# Spring12_6_Node.net
KiCad netlist of a schematic drawn in EAGLE
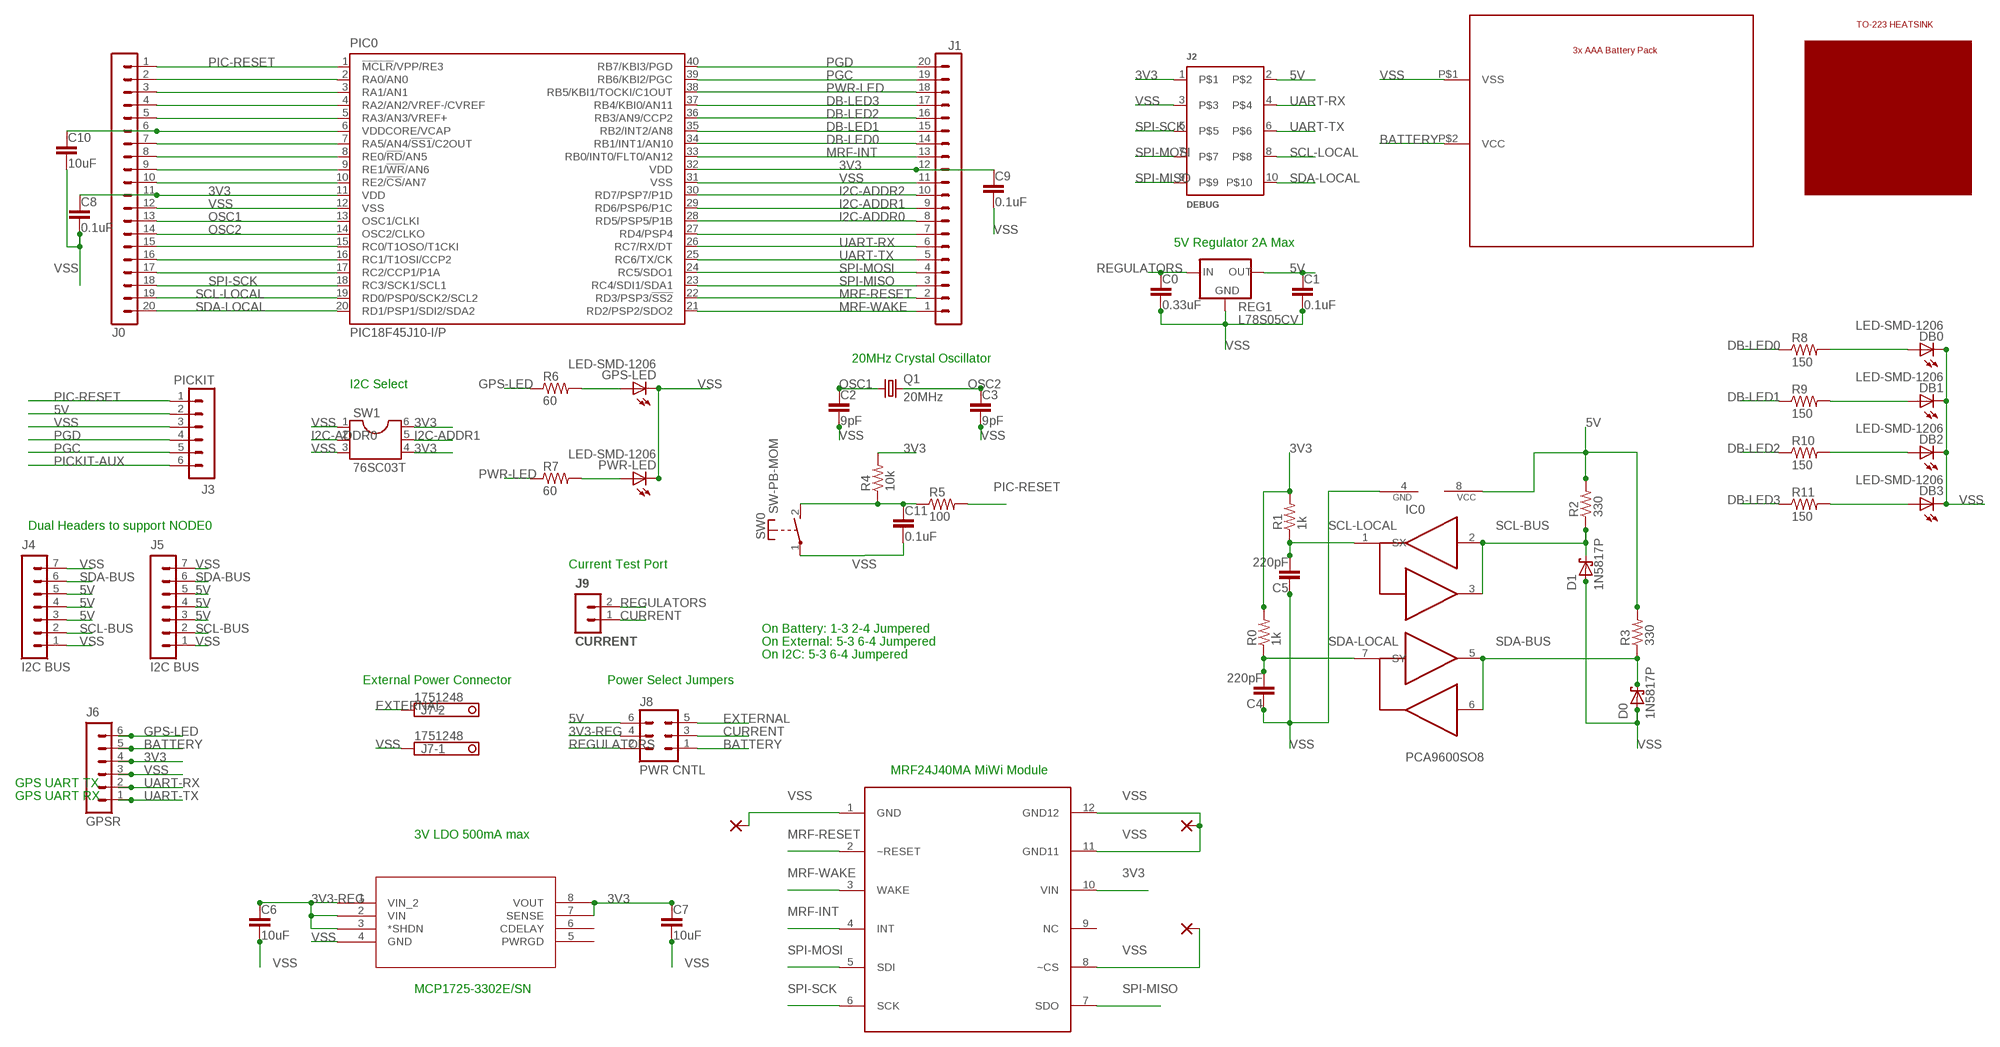
[diagram p0: schematic, sheet 1]

(export (version "E")
  (design (tool "Eeschema 10.0.6"))
  (components
    (comp (ref "BATT0")
      (value "2479-BATTERY")
      (footprint "eagle-import:2479-BATTERY")
      (libsource (lib "eagle-import") (part "2479-BATTERY"))
    )
    (comp (ref "C0")
      (value "0.33uF")
      (footprint "eagle-import:C2.5-5")
      (libsource (lib "eagle-import") (part "C2.5-5"))
    )
    (comp (ref "C1")
      (value "0.1uF")
      (footprint "eagle-import:C2.5-5")
      (libsource (lib "eagle-import") (part "C2.5-5"))
    )
    (comp (ref "C2")
      (value "9pF")
      (footprint "eagle-import:C2.5-5")
      (libsource (lib "eagle-import") (part "C2.5-5"))
    )
    (comp (ref "C3")
      (value "9pF")
      (footprint "eagle-import:C2.5-5")
      (libsource (lib "eagle-import") (part "C2.5-5"))
    )
    (comp (ref "C4")
      (value "220pF")
      (footprint "eagle-import:C2.5-5")
      (libsource (lib "eagle-import") (part "C2.5-5"))
    )
    (comp (ref "C5")
      (value "220pF")
      (footprint "eagle-import:C2.5-5")
      (libsource (lib "eagle-import") (part "C2.5-5"))
    )
    (comp (ref "C6")
      (value "10uF")
      (footprint "eagle-import:C2.5-5")
      (libsource (lib "eagle-import") (part "C2.5-5"))
    )
    (comp (ref "C7")
      (value "10uF")
      (footprint "eagle-import:C2.5-5")
      (libsource (lib "eagle-import") (part "C2.5-5"))
    )
    (comp (ref "C8")
      (value "0.1uF")
      (footprint "eagle-import:C2.5-5")
      (libsource (lib "eagle-import") (part "C2.5-5"))
    )
    (comp (ref "C9")
      (value "0.1uF")
      (footprint "eagle-import:C2.5-5")
      (libsource (lib "eagle-import") (part "C2.5-5"))
    )
    (comp (ref "C10")
      (value "10uF")
      (footprint "eagle-import:C2.5-5")
      (libsource (lib "eagle-import") (part "C2.5-5"))
    )
    (comp (ref "C11")
      (value "0.1uF")
      (footprint "eagle-import:C2.5-5")
      (libsource (lib "eagle-import") (part "C2.5-5"))
    )
    (comp (ref "D0")
      (value "1N5817P")
      (footprint "eagle-import:1N5817")
      (libsource (lib "eagle-import") (part "1N5817P"))
    )
    (comp (ref "D1")
      (value "1N5817P")
      (footprint "eagle-import:1N5817")
      (libsource (lib "eagle-import") (part "1N5817P"))
    )
    (comp (ref "DB0")
      (value "LED-SMD-1206")
      (footprint "eagle-import:LED1206")
      (libsource (lib "eagle-import") (part "LED-SMD-1206"))
    )
    (comp (ref "DB1")
      (value "LED-SMD-1206")
      (footprint "eagle-import:LED1206")
      (libsource (lib "eagle-import") (part "LED-SMD-1206"))
    )
    (comp (ref "DB2")
      (value "LED-SMD-1206")
      (footprint "eagle-import:LED1206")
      (libsource (lib "eagle-import") (part "LED-SMD-1206"))
    )
    (comp (ref "DB3")
      (value "LED-SMD-1206")
      (footprint "eagle-import:LED1206")
      (libsource (lib "eagle-import") (part "LED-SMD-1206"))
    )
    (comp (ref "GPS-LED")
      (value "LED-SMD-1206")
      (footprint "eagle-import:LED1206")
      (libsource (lib "eagle-import") (part "LED-SMD-1206"))
    )
    (comp (ref "IC0")
      (value "PCA9600SO8")
      (footprint "eagle-import:SO08")
      (libsource (lib "eagle-import") (part "PCA9600SO8"))
    )
    (comp (ref "J0")
      (value "MA20-1")
      (footprint "eagle-import:MA20-1")
      (fields (field (name "OC_FARNELL") "unknown") (field (name "OC_NEWARK") "unknown"))
      (libsource (lib "eagle-import") (part "MA20-1"))
    )
    (comp (ref "J1")
      (value "MA20-1")
      (footprint "eagle-import:MA20-1")
      (fields (field (name "OC_FARNELL") "unknown") (field (name "OC_NEWARK") "unknown"))
      (libsource (lib "eagle-import") (part "MA20-1"))
    )
    (comp (ref "J2")
      (value "DEBUG")
      (footprint "eagle-import:2510-6002")
      (libsource (lib "eagle-import") (part "2510-6002"))
    )
    (comp (ref "J3")
      (value "PICKIT")
      (footprint "eagle-import:MA06-1")
      (libsource (lib "eagle-import") (part "MA06-1"))
    )
    (comp (ref "J4")
      (value "I2C BUS")
      (footprint "eagle-import:MA07-1")
      (libsource (lib "eagle-import") (part "MA07-1"))
    )
    (comp (ref "J5")
      (value "I2C BUS")
      (footprint "eagle-import:MA07-1")
      (libsource (lib "eagle-import") (part "MA07-1"))
    )
    (comp (ref "J6")
      (value "GPSR")
      (footprint "eagle-import:MA06-1")
      (libsource (lib "eagle-import") (part "MA06-1"))
    )
    (comp (ref "J7")
      (value "1751248")
      (footprint "eagle-import:1751248")
      (libsource (lib "eagle-import") (part "1751248"))
    )
    (comp (ref "J8")
      (value "PWR CNTL")
      (footprint "eagle-import:MA03-2")
      (libsource (lib "eagle-import") (part "MA03-2"))
    )
    (comp (ref "J9")
      (value "CURRENT")
      (footprint "eagle-import:MA02-1")
      (libsource (lib "eagle-import") (part "MA02-1"))
    )
    (comp (ref "PIC0")
      (value "PIC18F45J10-I/P")
      (footprint "eagle-import:DIL40")
      (libsource (lib "eagle-import") (part "PIC18F45J10-I/P"))
    )
    (comp (ref "PWR-LED")
      (value "LED-SMD-1206")
      (footprint "eagle-import:LED1206")
      (libsource (lib "eagle-import") (part "LED-SMD-1206"))
    )
    (comp (ref "Q1")
      (value "20MHz")
      (footprint "eagle-import:HC49U-V")
      (libsource (lib "eagle-import") (part "CRYSTALHC49U-V"))
    )
    (comp (ref "R0")
      (value "1k")
      (footprint "eagle-import:R-1_4W")
      (libsource (lib "eagle-import") (part "R-1/4W"))
    )
    (comp (ref "R1")
      (value "1k")
      (footprint "eagle-import:R-1_4W")
      (libsource (lib "eagle-import") (part "R-1/4W"))
    )
    (comp (ref "R2")
      (value "330")
      (footprint "eagle-import:R-1_4W")
      (libsource (lib "eagle-import") (part "R-1/4W"))
    )
    (comp (ref "R3")
      (value "330")
      (footprint "eagle-import:R-1_4W")
      (libsource (lib "eagle-import") (part "R-1/4W"))
    )
    (comp (ref "R4")
      (value "10k")
      (footprint "eagle-import:R1206")
      (libsource (lib "eagle-import") (part "R1206"))
    )
    (comp (ref "R5")
      (value "100")
      (footprint "eagle-import:R1206")
      (libsource (lib "eagle-import") (part "R1206"))
    )
    (comp (ref "R6")
      (value "60")
      (footprint "eagle-import:R1206")
      (libsource (lib "eagle-import") (part "R1206"))
    )
    (comp (ref "R7")
      (value "60")
      (footprint "eagle-import:R1206")
      (libsource (lib "eagle-import") (part "R1206"))
    )
    (comp (ref "R8")
      (value "150")
      (footprint "eagle-import:R1206")
      (libsource (lib "eagle-import") (part "R1206"))
    )
    (comp (ref "R9")
      (value "150")
      (footprint "eagle-import:R1206")
      (libsource (lib "eagle-import") (part "R1206"))
    )
    (comp (ref "R10")
      (value "150")
      (footprint "eagle-import:R1206")
      (libsource (lib "eagle-import") (part "R1206"))
    )
    (comp (ref "R11")
      (value "150")
      (footprint "eagle-import:R1206")
      (libsource (lib "eagle-import") (part "R1206"))
    )
    (comp (ref "REG0")
      (value "MCP1725-XXXXX/SN")
      (footprint "eagle-import:SOIC8-N_MC")
      (libsource (lib "eagle-import") (part "MCP1725-XXXXX/SN"))
    )
    (comp (ref "REG1")
      (value "L78S05CV")
      (footprint "eagle-import:78XXL")
      (libsource (lib "eagle-import") (part "78XXL"))
    )
    (comp (ref "RF0")
      (value "MRF24J40MA")
      (footprint "eagle-import:PCB12")
      (libsource (lib "eagle-import") (part "MRF24J40MA"))
    )
    (comp (ref "SW0")
      (value "SW-PB-MOM")
      (footprint "eagle-import:SW-MOM-PB")
      (libsource (lib "eagle-import") (part "SW-PB-MOM"))
    )
    (comp (ref "SW1")
      (value "76SC03T")
      (footprint "eagle-import:DIL06")
      (libsource (lib "eagle-import") (part "DIL6"))
    )
    (comp (ref "U$18")
      (value "VIA")
      (footprint "eagle-import:VIA")
      (libsource (lib "eagle-import") (part "VIA"))
    )
    (comp (ref "U$19")
      (value "VIA")
      (footprint "eagle-import:VIA")
      (libsource (lib "eagle-import") (part "VIA"))
    )
    (comp (ref "U$20")
      (value "VIA")
      (footprint "eagle-import:VIA")
      (libsource (lib "eagle-import") (part "VIA"))
    )
    (comp (ref "U$28")
      (value "7-361-BA")
      (footprint "eagle-import:7-361-BA")
      (libsource (lib "eagle-import") (part "7-361-BA"))
    )
  )
  (nets
    (net (code "1") (name "/3V3") (class "Default")
      (node (ref "C7") (pin "1") (pinfunction "1_1") (pintype "passive"))
      (node (ref "C8") (pin "1") (pinfunction "1_1") (pintype "passive"))
      (node (ref "C9") (pin "1") (pinfunction "1_1") (pintype "passive"))
      (node (ref "J0") (pin "11") (pinfunction "11_11") (pintype "passive"))
      (node (ref "J1") (pin "12") (pinfunction "12_12") (pintype "passive"))
      (node (ref "J2") (pin "1") (pinfunction "P$1_1") (pintype "passive"))
      (node (ref "J6") (pin "4") (pinfunction "4_4") (pintype "passive"))
      (node (ref "PIC0") (pin "11") (pinfunction "VDD_11") (pintype "power_in"))
      (node (ref "PIC0") (pin "32") (pinfunction "VDD_32") (pintype "power_in"))
      (node (ref "R0") (pin "2") (pinfunction "2_2") (pintype "passive"))
      (node (ref "R1") (pin "2") (pinfunction "2_2") (pintype "passive"))
      (node (ref "R4") (pin "2") (pinfunction "2_2") (pintype "passive"))
      (node (ref "REG0") (pin "7") (pinfunction "SENSE_7") (pintype "passive"))
      (node (ref "REG0") (pin "8") (pinfunction "VOUT_8") (pintype "passive"))
      (node (ref "RF0") (pin "10") (pinfunction "VIN_10") (pintype "bidirectional"))
      (node (ref "SW1") (pin "4") (pinfunction "4_4") (pintype "passive"))
      (node (ref "SW1") (pin "6") (pinfunction "6_6") (pintype "passive"))
    )
    (net (code "2") (name "/3V3-REG") (class "Default")
      (node (ref "C6") (pin "1") (pinfunction "1_1") (pintype "passive"))
      (node (ref "J8") (pin "4") (pinfunction "4_4") (pintype "passive"))
      (node (ref "REG0") (pin "1") (pinfunction "VIN_2_1") (pintype "passive"))
      (node (ref "REG0") (pin "2") (pinfunction "VIN_2") (pintype "passive"))
      (node (ref "REG0") (pin "3") (pinfunction "*SHDN_3") (pintype "passive"))
    )
    (net (code "3") (name "/5V") (class "Default")
      (node (ref "C1") (pin "1") (pinfunction "1_1") (pintype "passive"))
      (node (ref "IC0") (pin "8") (pinfunction "VCC_8") (pintype "power_in"))
      (node (ref "J2") (pin "2") (pinfunction "P$2_2") (pintype "passive"))
      (node (ref "J3") (pin "2") (pinfunction "2_2") (pintype "passive"))
      (node (ref "J4") (pin "3") (pinfunction "3_3") (pintype "passive"))
      (node (ref "J4") (pin "4") (pinfunction "4_4") (pintype "passive"))
      (node (ref "J4") (pin "5") (pinfunction "5_5") (pintype "passive"))
      (node (ref "J5") (pin "3") (pinfunction "3_3") (pintype "passive"))
      (node (ref "J5") (pin "4") (pinfunction "4_4") (pintype "passive"))
      (node (ref "J5") (pin "5") (pinfunction "5_5") (pintype "passive"))
      (node (ref "J8") (pin "6") (pinfunction "6_6") (pintype "passive"))
      (node (ref "R2") (pin "2") (pinfunction "2_2") (pintype "passive"))
      (node (ref "R3") (pin "2") (pinfunction "2_2") (pintype "passive"))
      (node (ref "REG1") (pin "OUT") (pinfunction "OUT_OUT") (pintype "passive"))
    )
    (net (code "4") (name "/BATTERY") (class "Default")
      (node (ref "BATT0") (pin "P$2") (pinfunction "VCC_P$2") (pintype "bidirectional"))
      (node (ref "J6") (pin "5") (pinfunction "5_5") (pintype "passive"))
      (node (ref "J8") (pin "1") (pinfunction "1_1") (pintype "passive"))
    )
    (net (code "5") (name "/CURRENT") (class "Default")
      (node (ref "J8") (pin "3") (pinfunction "3_3") (pintype "passive"))
      (node (ref "J9") (pin "1") (pinfunction "1_1") (pintype "passive"))
    )
    (net (code "6") (name "/DB-LED0") (class "Default")
      (node (ref "J1") (pin "14") (pinfunction "14_14") (pintype "passive"))
      (node (ref "PIC0") (pin "34") (pinfunction "RB1/INT1/AN10_34") (pintype "bidirectional"))
      (node (ref "R8") (pin "1") (pinfunction "1_1") (pintype "passive"))
    )
    (net (code "7") (name "/DB-LED1") (class "Default")
      (node (ref "J1") (pin "15") (pinfunction "15_15") (pintype "passive"))
      (node (ref "PIC0") (pin "35") (pinfunction "RB2/INT2/AN8_35") (pintype "bidirectional"))
      (node (ref "R9") (pin "1") (pinfunction "1_1") (pintype "passive"))
    )
    (net (code "8") (name "/DB-LED2") (class "Default")
      (node (ref "J1") (pin "16") (pinfunction "16_16") (pintype "passive"))
      (node (ref "PIC0") (pin "36") (pinfunction "RB3/AN9/CCP2_36") (pintype "bidirectional"))
      (node (ref "R10") (pin "1") (pinfunction "1_1") (pintype "passive"))
    )
    (net (code "9") (name "/DB-LED3") (class "Default")
      (node (ref "J1") (pin "17") (pinfunction "17_17") (pintype "passive"))
      (node (ref "PIC0") (pin "37") (pinfunction "RB4/KBI0/AN11_37") (pintype "bidirectional"))
      (node (ref "R11") (pin "1") (pinfunction "1_1") (pintype "passive"))
    )
    (net (code "10") (name "/EXTERNAL") (class "Default")
      (node (ref "J7") (pin "2") (pinfunction "K_2") (pintype "passive"))
      (node (ref "J8") (pin "5") (pinfunction "5_5") (pintype "passive"))
    )
    (net (code "11") (name "/GPS-LED") (class "Default")
      (node (ref "J6") (pin "6") (pinfunction "6_6") (pintype "passive"))
      (node (ref "R6") (pin "1") (pinfunction "1_1") (pintype "passive"))
    )
    (net (code "12") (name "/I2C-ADDR0") (class "Default")
      (node (ref "J1") (pin "8") (pinfunction "8_8") (pintype "passive"))
      (node (ref "PIC0") (pin "28") (pinfunction "RD5/PSP5/P1B_28") (pintype "bidirectional"))
      (node (ref "SW1") (pin "2") (pinfunction "2_2") (pintype "passive"))
    )
    (net (code "13") (name "/I2C-ADDR1") (class "Default")
      (node (ref "J1") (pin "9") (pinfunction "9_9") (pintype "passive"))
      (node (ref "PIC0") (pin "29") (pinfunction "RD6/PSP6/P1C_29") (pintype "bidirectional"))
      (node (ref "SW1") (pin "5") (pinfunction "5_5") (pintype "passive"))
    )
    (net (code "14") (name "/I2C-ADDR2") (class "Default")
      (node (ref "J1") (pin "10") (pinfunction "10_10") (pintype "passive"))
      (node (ref "PIC0") (pin "30") (pinfunction "RD7/PSP7/P1D_30") (pintype "bidirectional"))
    )
    (net (code "15") (name "/MRF-INT") (class "Default")
      (node (ref "J1") (pin "13") (pinfunction "13_13") (pintype "passive"))
      (node (ref "PIC0") (pin "33") (pinfunction "RB0/INT0/FLT0/AN12_33") (pintype "bidirectional"))
      (node (ref "RF0") (pin "4") (pinfunction "INT_4") (pintype "bidirectional"))
    )
    (net (code "16") (name "/MRF-RESET") (class "Default")
      (node (ref "J1") (pin "2") (pinfunction "2_2") (pintype "passive"))
      (node (ref "PIC0") (pin "22") (pinfunction "RD3/PSP3/~{SS2}_22") (pintype "bidirectional"))
      (node (ref "RF0") (pin "2") (pinfunction "~{RESET}_2") (pintype "bidirectional"))
    )
    (net (code "17") (name "/MRF-WAKE") (class "Default")
      (node (ref "J1") (pin "1") (pinfunction "1_1") (pintype "passive"))
      (node (ref "PIC0") (pin "21") (pinfunction "RD2/PSP2/SDO2_21") (pintype "bidirectional"))
      (node (ref "RF0") (pin "3") (pinfunction "WAKE_3") (pintype "bidirectional"))
    )
    (net (code "18") (name "/OSC1") (class "Default")
      (node (ref "C2") (pin "1") (pinfunction "1_1") (pintype "passive"))
      (node (ref "J0") (pin "13") (pinfunction "13_13") (pintype "passive"))
      (node (ref "PIC0") (pin "13") (pinfunction "OSC1/CLKI_13") (pintype "input"))
      (node (ref "Q1") (pin "1") (pinfunction "1_1") (pintype "passive"))
    )
    (net (code "19") (name "/OSC2") (class "Default")
      (node (ref "C3") (pin "1") (pinfunction "1_1") (pintype "passive"))
      (node (ref "J0") (pin "14") (pinfunction "14_14") (pintype "passive"))
      (node (ref "PIC0") (pin "14") (pinfunction "OSC2/CLKO_14") (pintype "output"))
      (node (ref "Q1") (pin "2") (pinfunction "2_2") (pintype "passive"))
    )
    (net (code "20") (name "/PGC") (class "Default")
      (node (ref "J1") (pin "19") (pinfunction "19_19") (pintype "passive"))
      (node (ref "J3") (pin "5") (pinfunction "5_5") (pintype "passive"))
      (node (ref "PIC0") (pin "39") (pinfunction "RB6/KBI2/PGC_39") (pintype "bidirectional"))
    )
    (net (code "21") (name "/PGD") (class "Default")
      (node (ref "J1") (pin "20") (pinfunction "20_20") (pintype "passive"))
      (node (ref "J3") (pin "4") (pinfunction "4_4") (pintype "passive"))
      (node (ref "PIC0") (pin "40") (pinfunction "RB7/KBI3/PGD_40") (pintype "bidirectional"))
    )
    (net (code "22") (name "/PIC-RESET") (class "Default")
      (node (ref "J0") (pin "1") (pinfunction "1_1") (pintype "passive"))
      (node (ref "J3") (pin "1") (pinfunction "1_1") (pintype "passive"))
      (node (ref "PIC0") (pin "1") (pinfunction "~{MCLR}/VPP/RE3_1") (pintype "input"))
      (node (ref "R5") (pin "2") (pinfunction "2_2") (pintype "passive"))
    )
    (net (code "23") (name "/PICKIT-AUX") (class "Default")
      (node (ref "J3") (pin "6") (pinfunction "6_6") (pintype "passive"))
    )
    (net (code "24") (name "/PWR-LED") (class "Default")
      (node (ref "J1") (pin "18") (pinfunction "18_18") (pintype "passive"))
      (node (ref "PIC0") (pin "38") (pinfunction "RB5/KBI1/TOCKI/C1OUT_38") (pintype "bidirectional"))
      (node (ref "R7") (pin "1") (pinfunction "1_1") (pintype "passive"))
    )
    (net (code "25") (name "/REGULATORS") (class "Default")
      (node (ref "C0") (pin "1") (pinfunction "1_1") (pintype "passive"))
      (node (ref "J8") (pin "2") (pinfunction "2_2") (pintype "passive"))
      (node (ref "J9") (pin "2") (pinfunction "2_2") (pintype "passive"))
      (node (ref "REG1") (pin "IN") (pinfunction "IN_IN") (pintype "input"))
    )
    (net (code "26") (name "/SCL-BUS") (class "Default")
      (node (ref "D1") (pin "C") (pinfunction "C_C") (pintype "passive"))
      (node (ref "IC0") (pin "2") (pinfunction "RX_2") (pintype "input"))
      (node (ref "IC0") (pin "3") (pinfunction "TX_3") (pintype "output"))
      (node (ref "J4") (pin "2") (pinfunction "2_2") (pintype "passive"))
      (node (ref "J5") (pin "2") (pinfunction "2_2") (pintype "passive"))
      (node (ref "R2") (pin "1") (pinfunction "1_1") (pintype "passive"))
    )
    (net (code "27") (name "/SCL-LOCAL") (class "Default")
      (node (ref "C5") (pin "2") (pinfunction "2_2") (pintype "passive"))
      (node (ref "IC0") (pin "1") (pinfunction "SX_1") (pintype "bidirectional"))
      (node (ref "J0") (pin "19") (pinfunction "19_19") (pintype "passive"))
      (node (ref "J2") (pin "8") (pinfunction "P$8_8") (pintype "passive"))
      (node (ref "PIC0") (pin "19") (pinfunction "RD0/PSP0/SCK2/SCL2_19") (pintype "bidirectional"))
      (node (ref "R1") (pin "1") (pinfunction "1_1") (pintype "passive"))
    )
    (net (code "28") (name "/SDA-BUS") (class "Default")
      (node (ref "D0") (pin "C") (pinfunction "C_C") (pintype "passive"))
      (node (ref "IC0") (pin "5") (pinfunction "TY_5") (pintype "output"))
      (node (ref "IC0") (pin "6") (pinfunction "RY_6") (pintype "input"))
      (node (ref "J4") (pin "6") (pinfunction "6_6") (pintype "passive"))
      (node (ref "J5") (pin "6") (pinfunction "6_6") (pintype "passive"))
      (node (ref "R3") (pin "1") (pinfunction "1_1") (pintype "passive"))
    )
    (net (code "29") (name "/SDA-LOCAL") (class "Default")
      (node (ref "C4") (pin "2") (pinfunction "2_2") (pintype "passive"))
      (node (ref "IC0") (pin "7") (pinfunction "SY_7") (pintype "bidirectional"))
      (node (ref "J0") (pin "20") (pinfunction "20_20") (pintype "passive"))
      (node (ref "J2") (pin "10") (pinfunction "P$10_10") (pintype "passive"))
      (node (ref "PIC0") (pin "20") (pinfunction "RD1/PSP1/SDI2/SDA2_20") (pintype "bidirectional"))
      (node (ref "R0") (pin "1") (pinfunction "1_1") (pintype "passive"))
    )
    (net (code "30") (name "/SPI-MISO") (class "Default")
      (node (ref "J1") (pin "3") (pinfunction "3_3") (pintype "passive"))
      (node (ref "J2") (pin "9") (pinfunction "P$9_9") (pintype "passive"))
      (node (ref "PIC0") (pin "23") (pinfunction "RC4/SDI1/SDA1_23") (pintype "bidirectional"))
      (node (ref "RF0") (pin "7") (pinfunction "SDO_7") (pintype "bidirectional"))
    )
    (net (code "31") (name "/SPI-MOSI") (class "Default")
      (node (ref "J1") (pin "4") (pinfunction "4_4") (pintype "passive"))
      (node (ref "J2") (pin "7") (pinfunction "P$7_7") (pintype "passive"))
      (node (ref "PIC0") (pin "24") (pinfunction "RC5/SDO1_24") (pintype "bidirectional"))
      (node (ref "RF0") (pin "5") (pinfunction "SDI_5") (pintype "bidirectional"))
    )
    (net (code "32") (name "/SPI-SCK") (class "Default")
      (node (ref "J0") (pin "18") (pinfunction "18_18") (pintype "passive"))
      (node (ref "J2") (pin "5") (pinfunction "P$5_5") (pintype "passive"))
      (node (ref "PIC0") (pin "18") (pinfunction "RC3/SCK1/SCL1_18") (pintype "bidirectional"))
      (node (ref "RF0") (pin "6") (pinfunction "SCK_6") (pintype "bidirectional"))
    )
    (net (code "33") (name "/UART-RX") (class "Default")
      (node (ref "J1") (pin "6") (pinfunction "6_6") (pintype "passive"))
      (node (ref "J2") (pin "4") (pinfunction "P$4_4") (pintype "passive"))
      (node (ref "J6") (pin "2") (pinfunction "2_2") (pintype "passive"))
      (node (ref "PIC0") (pin "26") (pinfunction "RC7/RX/DT_26") (pintype "bidirectional"))
    )
    (net (code "34") (name "/UART-TX") (class "Default")
      (node (ref "J1") (pin "5") (pinfunction "5_5") (pintype "passive"))
      (node (ref "J2") (pin "6") (pinfunction "P$6_6") (pintype "passive"))
      (node (ref "J6") (pin "1") (pinfunction "1_1") (pintype "passive"))
      (node (ref "PIC0") (pin "25") (pinfunction "RC6/TX/CK_25") (pintype "bidirectional"))
    )
    (net (code "35") (name "/VSS") (class "Default")
      (node (ref "BATT0") (pin "P$1") (pinfunction "VSS_P$1") (pintype "bidirectional"))
      (node (ref "C0") (pin "2") (pinfunction "2_2") (pintype "passive"))
      (node (ref "C1") (pin "2") (pinfunction "2_2") (pintype "passive"))
      (node (ref "C10") (pin "2") (pinfunction "2_2") (pintype "passive"))
      (node (ref "C11") (pin "2") (pinfunction "2_2") (pintype "passive"))
      (node (ref "C2") (pin "2") (pinfunction "2_2") (pintype "passive"))
      (node (ref "C3") (pin "2") (pinfunction "2_2") (pintype "passive"))
      (node (ref "C4") (pin "1") (pinfunction "1_1") (pintype "passive"))
      (node (ref "C5") (pin "1") (pinfunction "1_1") (pintype "passive"))
      (node (ref "C6") (pin "2") (pinfunction "2_2") (pintype "passive"))
      (node (ref "C7") (pin "2") (pinfunction "2_2") (pintype "passive"))
      (node (ref "C8") (pin "2") (pinfunction "2_2") (pintype "passive"))
      (node (ref "C9") (pin "2") (pinfunction "2_2") (pintype "passive"))
      (node (ref "D0") (pin "A") (pinfunction "A_A") (pintype "passive"))
      (node (ref "D1") (pin "A") (pinfunction "A_A") (pintype "passive"))
      (node (ref "DB0") (pin "C") (pinfunction "C_C") (pintype "passive"))
      (node (ref "DB1") (pin "C") (pinfunction "C_C") (pintype "passive"))
      (node (ref "DB2") (pin "C") (pinfunction "C_C") (pintype "passive"))
      (node (ref "DB3") (pin "C") (pinfunction "C_C") (pintype "passive"))
      (node (ref "GPS-LED") (pin "C") (pinfunction "C_C") (pintype "passive"))
      (node (ref "IC0") (pin "4") (pinfunction "GND_4") (pintype "power_in"))
      (node (ref "J0") (pin "12") (pinfunction "12_12") (pintype "passive"))
      (node (ref "J1") (pin "11") (pinfunction "11_11") (pintype "passive"))
      (node (ref "J2") (pin "3") (pinfunction "P$3_3") (pintype "passive"))
      (node (ref "J3") (pin "3") (pinfunction "3_3") (pintype "passive"))
      (node (ref "J4") (pin "1") (pinfunction "1_1") (pintype "passive"))
      (node (ref "J4") (pin "7") (pinfunction "7_7") (pintype "passive"))
      (node (ref "J5") (pin "1") (pinfunction "1_1") (pintype "passive"))
      (node (ref "J5") (pin "7") (pinfunction "7_7") (pintype "passive"))
      (node (ref "J6") (pin "3") (pinfunction "3_3") (pintype "passive"))
      (node (ref "J7") (pin "1") (pinfunction "K_1") (pintype "passive"))
      (node (ref "PIC0") (pin "12") (pinfunction "VSS_12") (pintype "power_in"))
      (node (ref "PIC0") (pin "31") (pinfunction "VSS_31") (pintype "power_in"))
      (node (ref "PWR-LED") (pin "C") (pinfunction "C_C") (pintype "passive"))
      (node (ref "REG0") (pin "4") (pinfunction "GND_4") (pintype "passive"))
      (node (ref "REG1") (pin "GND") (pinfunction "GND_GND") (pintype "input"))
      (node (ref "RF0") (pin "1") (pinfunction "GND_1") (pintype "bidirectional"))
      (node (ref "RF0") (pin "11") (pinfunction "GND11_11") (pintype "bidirectional"))
      (node (ref "RF0") (pin "12") (pinfunction "GND12_12") (pintype "bidirectional"))
      (node (ref "RF0") (pin "8") (pinfunction "~{CS}_8") (pintype "bidirectional"))
      (node (ref "SW0") (pin "1") (pinfunction "P_1") (pintype "passive"))
      (node (ref "SW1") (pin "1") (pinfunction "1_1") (pintype "passive"))
      (node (ref "SW1") (pin "3") (pinfunction "3_3") (pintype "passive"))
      (node (ref "U$18") (pin "1") (pinfunction "P_1") (pintype "passive"))
      (node (ref "U$19") (pin "1") (pinfunction "P_1") (pintype "passive"))
      (node (ref "U$20") (pin "1") (pinfunction "P_1") (pintype "passive"))
    )
    (net (code "36") (name "Net-(DB0-PadA)") (class "Default")
      (node (ref "DB0") (pin "A") (pinfunction "A_A") (pintype "passive"))
      (node (ref "R8") (pin "2") (pinfunction "2_2") (pintype "passive"))
    )
    (net (code "37") (name "Net-(DB1-PadA)") (class "Default")
      (node (ref "DB1") (pin "A") (pinfunction "A_A") (pintype "passive"))
      (node (ref "R9") (pin "2") (pinfunction "2_2") (pintype "passive"))
    )
    (net (code "38") (name "Net-(DB2-PadA)") (class "Default")
      (node (ref "DB2") (pin "A") (pinfunction "A_A") (pintype "passive"))
      (node (ref "R10") (pin "2") (pinfunction "2_2") (pintype "passive"))
    )
    (net (code "39") (name "Net-(DB3-PadA)") (class "Default")
      (node (ref "DB3") (pin "A") (pinfunction "A_A") (pintype "passive"))
      (node (ref "R11") (pin "2") (pinfunction "2_2") (pintype "passive"))
    )
    (net (code "40") (name "Net-(GPS-LED-PadA)") (class "Default")
      (node (ref "GPS-LED") (pin "A") (pinfunction "A_A") (pintype "passive"))
      (node (ref "R6") (pin "2") (pinfunction "2_2") (pintype "passive"))
    )
    (net (code "41") (name "Net-(PIC0-RA0{slash}AN0)") (class "Default")
      (node (ref "J0") (pin "2") (pinfunction "2_2") (pintype "passive"))
      (node (ref "PIC0") (pin "2") (pinfunction "RA0/AN0_2") (pintype "bidirectional"))
    )
    (net (code "42") (name "Net-(PIC0-RA1{slash}AN1)") (class "Default")
      (node (ref "J0") (pin "3") (pinfunction "3_3") (pintype "passive"))
      (node (ref "PIC0") (pin "3") (pinfunction "RA1/AN1_3") (pintype "bidirectional"))
    )
    (net (code "43") (name "Net-(PIC0-RA2{slash}AN2{slash}VREF-{slash}CVREF)") (class "Default")
      (node (ref "J0") (pin "4") (pinfunction "4_4") (pintype "passive"))
      (node (ref "PIC0") (pin "4") (pinfunction "RA2/AN2/VREF-/CVREF_4") (pintype "bidirectional"))
    )
    (net (code "44") (name "Net-(PIC0-RA3{slash}AN3{slash}VREF+)") (class "Default")
      (node (ref "J0") (pin "5") (pinfunction "5_5") (pintype "passive"))
      (node (ref "PIC0") (pin "5") (pinfunction "RA3/AN3/VREF+_5") (pintype "bidirectional"))
    )
    (net (code "45") (name "Net-(PIC0-RA5{slash}AN4{slash}~{SS1}{slash}C2OUT)") (class "Default")
      (node (ref "J0") (pin "7") (pinfunction "7_7") (pintype "passive"))
      (node (ref "PIC0") (pin "7") (pinfunction "RA5/AN4/~{SS1}/C2OUT_7") (pintype "bidirectional"))
    )
    (net (code "46") (name "Net-(PIC0-RC0{slash}T1OSO{slash}T1CKI)") (class "Default")
      (node (ref "J0") (pin "15") (pinfunction "15_15") (pintype "passive"))
      (node (ref "PIC0") (pin "15") (pinfunction "RC0/T1OSO/T1CKI_15") (pintype "bidirectional"))
    )
    (net (code "47") (name "Net-(PIC0-RC1{slash}T1OSI{slash}CCP2)") (class "Default")
      (node (ref "J0") (pin "16") (pinfunction "16_16") (pintype "passive"))
      (node (ref "PIC0") (pin "16") (pinfunction "RC1/T1OSI/CCP2_16") (pintype "bidirectional"))
    )
    (net (code "48") (name "Net-(PIC0-RC2{slash}CCP1{slash}P1A)") (class "Default")
      (node (ref "J0") (pin "17") (pinfunction "17_17") (pintype "passive"))
      (node (ref "PIC0") (pin "17") (pinfunction "RC2/CCP1/P1A_17") (pintype "bidirectional"))
    )
    (net (code "49") (name "Net-(PIC0-RD4{slash}PSP4)") (class "Default")
      (node (ref "J1") (pin "7") (pinfunction "7_7") (pintype "passive"))
      (node (ref "PIC0") (pin "27") (pinfunction "RD4/PSP4_27") (pintype "bidirectional"))
    )
    (net (code "50") (name "Net-(PIC0-RE0{slash}~{RD}{slash}AN5)") (class "Default")
      (node (ref "J0") (pin "8") (pinfunction "8_8") (pintype "passive"))
      (node (ref "PIC0") (pin "8") (pinfunction "RE0/~{RD}/AN5_8") (pintype "bidirectional"))
    )
    (net (code "51") (name "Net-(PIC0-RE1{slash}~{WR}{slash}AN6)") (class "Default")
      (node (ref "J0") (pin "9") (pinfunction "9_9") (pintype "passive"))
      (node (ref "PIC0") (pin "9") (pinfunction "RE1/~{WR}/AN6_9") (pintype "bidirectional"))
    )
    (net (code "52") (name "Net-(PIC0-RE2{slash}~{CS}{slash}AN7)") (class "Default")
      (node (ref "J0") (pin "10") (pinfunction "10_10") (pintype "passive"))
      (node (ref "PIC0") (pin "10") (pinfunction "RE2/~{CS}/AN7_10") (pintype "bidirectional"))
    )
    (net (code "53") (name "Net-(PIC0-VDDCORE{slash}VCAP)") (class "Default")
      (node (ref "C10") (pin "1") (pinfunction "1_1") (pintype "passive"))
      (node (ref "J0") (pin "6") (pinfunction "6_6") (pintype "passive"))
      (node (ref "PIC0") (pin "6") (pinfunction "VDDCORE/VCAP_6") (pintype "bidirectional"))
    )
    (net (code "54") (name "Net-(PWR-LED-PadA)") (class "Default")
      (node (ref "PWR-LED") (pin "A") (pinfunction "A_A") (pintype "passive"))
      (node (ref "R7") (pin "2") (pinfunction "2_2") (pintype "passive"))
    )
    (net (code "55") (name "Net-(SW0-S)") (class "Default")
      (node (ref "C11") (pin "1") (pinfunction "1_1") (pintype "passive"))
      (node (ref "R4") (pin "1") (pinfunction "1_1") (pintype "passive"))
      (node (ref "R5") (pin "1") (pinfunction "1_1") (pintype "passive"))
      (node (ref "SW0") (pin "2") (pinfunction "S_2") (pintype "passive"))
    )
    (net (code "56") (name "unconnected-(REG0-CDELAY-Pad6)") (class "Default")
      (node (ref "REG0") (pin "6") (pinfunction "CDELAY_6") (pintype "passive"))
    )
    (net (code "57") (name "unconnected-(REG0-PWRGD-Pad5)") (class "Default")
      (node (ref "REG0") (pin "5") (pinfunction "PWRGD_5") (pintype "passive"))
    )
    (net (code "58") (name "unconnected-(RF0-NC-Pad9)") (class "Default")
      (node (ref "RF0") (pin "9") (pinfunction "NC_9") (pintype "bidirectional"))
    )
  )
)
